# racing_unit.net
KiCad netlist of a schematic drawn in EAGLE
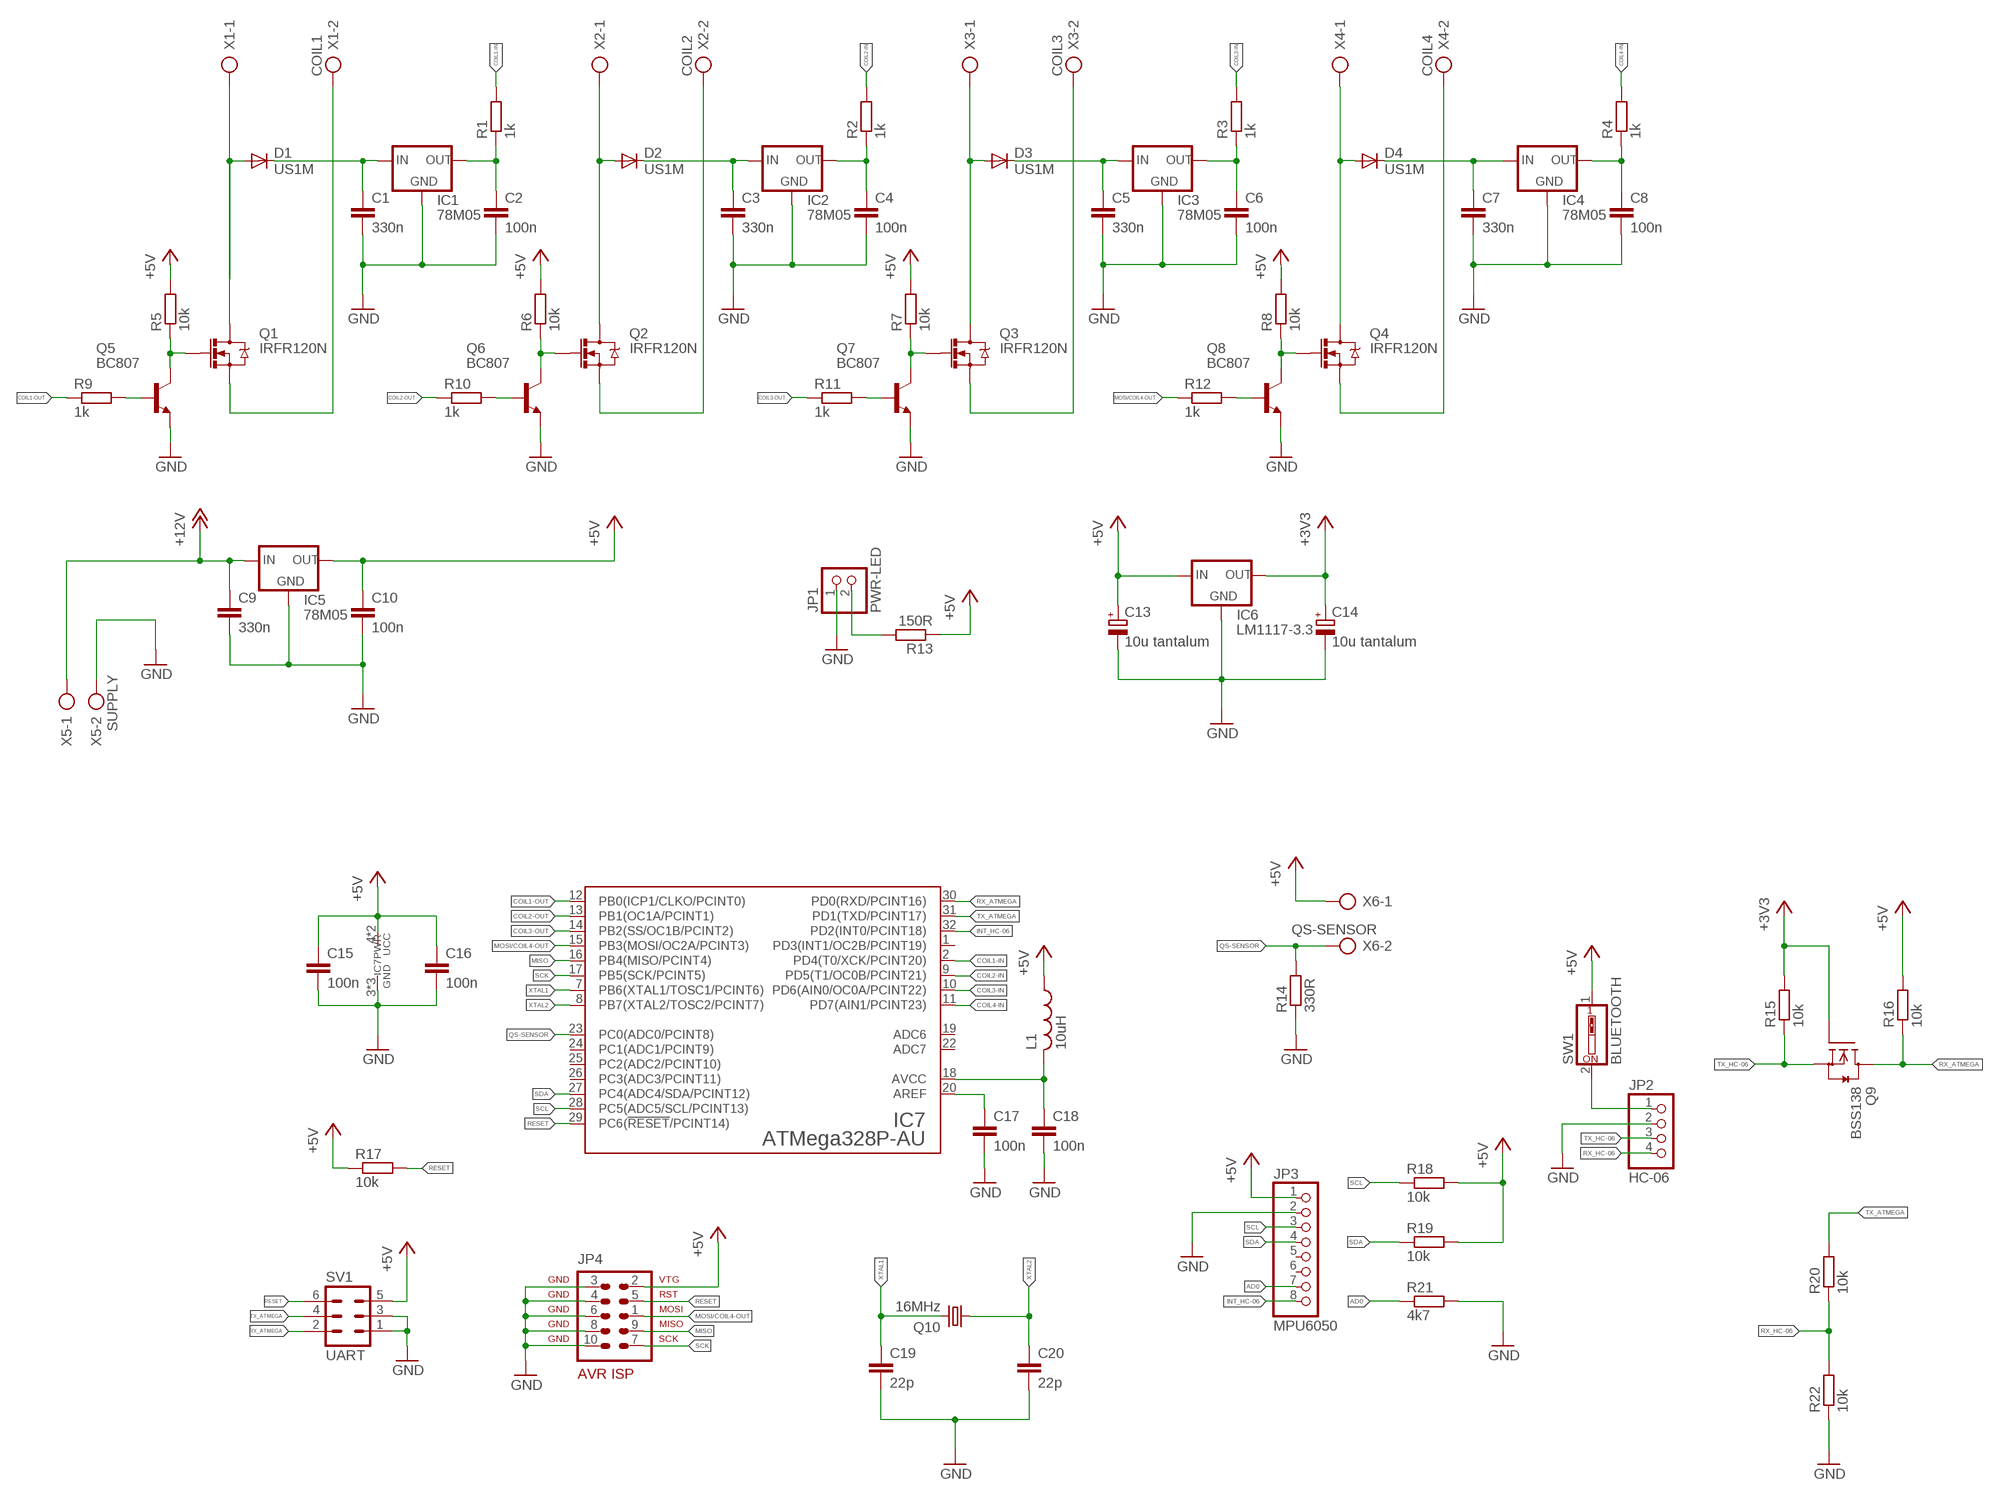
[diagram p0: schematic, sheet 1]

(export (version "E")
  (design (tool "Eeschema 10.0.6"))
  (components
    (comp (ref "C1")
      (value "330n")
      (footprint "eagle-import:C0805")
      (libsource (lib "eagle-import") (part "C-EUC0805"))
    )
    (comp (ref "C2")
      (value "100n")
      (footprint "eagle-import:C0805")
      (libsource (lib "eagle-import") (part "C-EUC0805"))
    )
    (comp (ref "C3")
      (value "330n")
      (footprint "eagle-import:C0805")
      (libsource (lib "eagle-import") (part "C-EUC0805"))
    )
    (comp (ref "C4")
      (value "100n")
      (footprint "eagle-import:C0805")
      (libsource (lib "eagle-import") (part "C-EUC0805"))
    )
    (comp (ref "C5")
      (value "330n")
      (footprint "eagle-import:C0805")
      (libsource (lib "eagle-import") (part "C-EUC0805"))
    )
    (comp (ref "C6")
      (value "100n")
      (footprint "eagle-import:C0805")
      (libsource (lib "eagle-import") (part "C-EUC0805"))
    )
    (comp (ref "C7")
      (value "330n")
      (footprint "eagle-import:C0805")
      (libsource (lib "eagle-import") (part "C-EUC0805"))
    )
    (comp (ref "C8")
      (value "100n")
      (footprint "eagle-import:C0805")
      (libsource (lib "eagle-import") (part "C-EUC0805"))
    )
    (comp (ref "C9")
      (value "330n")
      (footprint "eagle-import:C0805")
      (libsource (lib "eagle-import") (part "C-EUC0805"))
    )
    (comp (ref "C10")
      (value "100n")
      (footprint "eagle-import:C0805")
      (libsource (lib "eagle-import") (part "C-EUC0805"))
    )
    (comp (ref "C13")
      (value "10u tantalum")
      (footprint "eagle-import:A_3216-18R")
      (libsource (lib "eagle-import") (part "CPOL-EUA/3216-18R"))
    )
    (comp (ref "C14")
      (value "10u tantalum")
      (footprint "eagle-import:A_3216-18R")
      (libsource (lib "eagle-import") (part "CPOL-EUA/3216-18R"))
    )
    (comp (ref "C15")
      (value "100n")
      (footprint "eagle-import:C0805")
      (libsource (lib "eagle-import") (part "C-EUC0805"))
    )
    (comp (ref "C16")
      (value "100n")
      (footprint "eagle-import:C0805")
      (libsource (lib "eagle-import") (part "C-EUC0805"))
    )
    (comp (ref "C17")
      (value "100n")
      (footprint "eagle-import:C0805")
      (libsource (lib "eagle-import") (part "C-EUC0805"))
    )
    (comp (ref "C18")
      (value "100n")
      (footprint "eagle-import:C0805")
      (libsource (lib "eagle-import") (part "C-EUC0805"))
    )
    (comp (ref "C19")
      (value "22p")
      (footprint "eagle-import:C0805")
      (libsource (lib "eagle-import") (part "C-EUC0805"))
    )
    (comp (ref "C20")
      (value "22p")
      (footprint "eagle-import:C0805")
      (libsource (lib "eagle-import") (part "C-EUC0805"))
    )
    (comp (ref "D1")
      (value "US1M")
      (footprint "eagle-import:DO214AC")
      (libsource (lib "eagle-import") (part "DIODE-DO214AC"))
    )
    (comp (ref "D2")
      (value "US1M")
      (footprint "eagle-import:DO214AC")
      (libsource (lib "eagle-import") (part "DIODE-DO214AC"))
    )
    (comp (ref "D3")
      (value "US1M")
      (footprint "eagle-import:DO214AC")
      (libsource (lib "eagle-import") (part "DIODE-DO214AC"))
    )
    (comp (ref "D4")
      (value "US1M")
      (footprint "eagle-import:DO214AC")
      (libsource (lib "eagle-import") (part "DIODE-DO214AC"))
    )
    (comp (ref "IC1")
      (value "78M05")
      (footprint "eagle-import:TO252")
      (libsource (lib "eagle-import") (part "LM1117TO252"))
    )
    (comp (ref "IC2")
      (value "78M05")
      (footprint "eagle-import:TO252")
      (libsource (lib "eagle-import") (part "LM1117TO252"))
    )
    (comp (ref "IC3")
      (value "78M05")
      (footprint "eagle-import:TO252")
      (libsource (lib "eagle-import") (part "LM1117TO252"))
    )
    (comp (ref "IC4")
      (value "78M05")
      (footprint "eagle-import:TO252")
      (libsource (lib "eagle-import") (part "LM1117TO252"))
    )
    (comp (ref "IC5")
      (value "78M05")
      (footprint "eagle-import:TO252")
      (libsource (lib "eagle-import") (part "LM1117TO252"))
    )
    (comp (ref "IC6")
      (value "LM1117-3.3")
      (footprint "eagle-import:SOT223")
      (libsource (lib "eagle-import") (part "LM1117"))
    )
    (comp (ref "IC7")
      (value "ATMega328P-AU")
      (footprint "eagle-import:TQFP32-08")
      (libsource (lib "eagle-import") (part "ATMEGA48/88/168/328-AU"))
    )
    (comp (ref "JP1")
      (value "PWR-LED")
      (footprint "eagle-import:1X02")
      (libsource (lib "eagle-import") (part "PINHD-1X2"))
    )
    (comp (ref "JP2")
      (value "HC-06")
      (footprint "eagle-import:1X04")
      (libsource (lib "eagle-import") (part "PINHD-1X4"))
    )
    (comp (ref "JP3")
      (value "MPU6050")
      (footprint "eagle-import:1X08")
      (libsource (lib "eagle-import") (part "PINHD-1X8"))
    )
    (comp (ref "JP4")
      (value "AVR-ISP-10ML")
      (footprint "eagle-import:ML10")
      (libsource (lib "eagle-import") (part "AVR-ISP-10ML"))
    )
    (comp (ref "L1")
      (value "10uH")
      (footprint "eagle-import:0207_10")
      (libsource (lib "eagle-import") (part "L-US0207/10"))
    )
    (comp (ref "Q1")
      (value "IRFR120N")
      (footprint "eagle-import:D-PAK_TO252AA")
      (libsource (lib "eagle-import") (part "MOSFET-NCHANNEL_D-PAK"))
    )
    (comp (ref "Q2")
      (value "IRFR120N")
      (footprint "eagle-import:D-PAK_TO252AA")
      (libsource (lib "eagle-import") (part "MOSFET-NCHANNEL_D-PAK"))
    )
    (comp (ref "Q3")
      (value "IRFR120N")
      (footprint "eagle-import:D-PAK_TO252AA")
      (libsource (lib "eagle-import") (part "MOSFET-NCHANNEL_D-PAK"))
    )
    (comp (ref "Q4")
      (value "IRFR120N")
      (footprint "eagle-import:D-PAK_TO252AA")
      (libsource (lib "eagle-import") (part "MOSFET-NCHANNEL_D-PAK"))
    )
    (comp (ref "Q5")
      (value "BC807")
      (footprint "eagle-import:SOT23-BEC")
      (libsource (lib "eagle-import") (part "BC817SMD-16LT1"))
    )
    (comp (ref "Q6")
      (value "BC807")
      (footprint "eagle-import:SOT23-BEC")
      (libsource (lib "eagle-import") (part "BC817SMD-16LT1"))
    )
    (comp (ref "Q7")
      (value "BC807")
      (footprint "eagle-import:SOT23-BEC")
      (libsource (lib "eagle-import") (part "BC817SMD-16LT1"))
    )
    (comp (ref "Q8")
      (value "BC807")
      (footprint "eagle-import:SOT23-BEC")
      (libsource (lib "eagle-import") (part "BC817SMD-16LT1"))
    )
    (comp (ref "Q9")
      (value "BSS138")
      (footprint "eagle-import:SOT23")
      (libsource (lib "eagle-import") (part "BSS138"))
    )
    (comp (ref "Q10")
      (value "16MHz")
      (footprint "eagle-import:HC49_S")
      (libsource (lib "eagle-import") (part "CRYSTALHC49S"))
    )
    (comp (ref "R1")
      (value "1k")
      (footprint "eagle-import:M0805")
      (libsource (lib "eagle-import") (part "R-EU_M0805"))
    )
    (comp (ref "R2")
      (value "1k")
      (footprint "eagle-import:M0805")
      (libsource (lib "eagle-import") (part "R-EU_M0805"))
    )
    (comp (ref "R3")
      (value "1k")
      (footprint "eagle-import:M0805")
      (libsource (lib "eagle-import") (part "R-EU_M0805"))
    )
    (comp (ref "R4")
      (value "1k")
      (footprint "eagle-import:M0805")
      (libsource (lib "eagle-import") (part "R-EU_M0805"))
    )
    (comp (ref "R5")
      (value "10k")
      (footprint "eagle-import:M0805")
      (libsource (lib "eagle-import") (part "R-EU_M0805"))
    )
    (comp (ref "R6")
      (value "10k")
      (footprint "eagle-import:M0805")
      (libsource (lib "eagle-import") (part "R-EU_M0805"))
    )
    (comp (ref "R7")
      (value "10k")
      (footprint "eagle-import:M0805")
      (libsource (lib "eagle-import") (part "R-EU_M0805"))
    )
    (comp (ref "R8")
      (value "10k")
      (footprint "eagle-import:M0805")
      (libsource (lib "eagle-import") (part "R-EU_M0805"))
    )
    (comp (ref "R9")
      (value "1k")
      (footprint "eagle-import:M0805")
      (libsource (lib "eagle-import") (part "R-EU_M0805"))
    )
    (comp (ref "R10")
      (value "1k")
      (footprint "eagle-import:M0805")
      (libsource (lib "eagle-import") (part "R-EU_M0805"))
    )
    (comp (ref "R11")
      (value "1k")
      (footprint "eagle-import:M0805")
      (libsource (lib "eagle-import") (part "R-EU_M0805"))
    )
    (comp (ref "R12")
      (value "1k")
      (footprint "eagle-import:M0805")
      (libsource (lib "eagle-import") (part "R-EU_M0805"))
    )
    (comp (ref "R13")
      (value "150R")
      (footprint "eagle-import:0204_5")
      (libsource (lib "eagle-import") (part "resistor_R-EU_0204/5"))
    )
    (comp (ref "R14")
      (value "330R")
      (footprint "eagle-import:0204_5")
      (libsource (lib "eagle-import") (part "resistor_R-EU_0204/5"))
    )
    (comp (ref "R15")
      (value "10k")
      (footprint "eagle-import:M0805")
      (libsource (lib "eagle-import") (part "R-EU_M0805"))
    )
    (comp (ref "R16")
      (value "10k")
      (footprint "eagle-import:M0805")
      (libsource (lib "eagle-import") (part "R-EU_M0805"))
    )
    (comp (ref "R17")
      (value "10k")
      (footprint "eagle-import:M0805")
      (libsource (lib "eagle-import") (part "R-EU_M0805"))
    )
    (comp (ref "R18")
      (value "10k")
      (footprint "eagle-import:M0805")
      (libsource (lib "eagle-import") (part "R-EU_M0805"))
    )
    (comp (ref "R19")
      (value "10k")
      (footprint "eagle-import:M0805")
      (libsource (lib "eagle-import") (part "R-EU_M0805"))
    )
    (comp (ref "R20")
      (value "10k")
      (footprint "eagle-import:M0805")
      (libsource (lib "eagle-import") (part "R-EU_M0805"))
    )
    (comp (ref "R21")
      (value "4k7")
      (footprint "eagle-import:M0805")
      (libsource (lib "eagle-import") (part "R-EU_M0805"))
    )
    (comp (ref "R22")
      (value "10k")
      (footprint "eagle-import:M0805")
      (libsource (lib "eagle-import") (part "R-EU_M0805"))
    )
    (comp (ref "SV1")
      (value "UART")
      (footprint "eagle-import:ML6")
      (libsource (lib "eagle-import") (part "ML6"))
    )
    (comp (ref "SW1")
      (value "BLUETOOTH")
      (footprint "eagle-import:EDG-01")
      (libsource (lib "eagle-import") (part "SW_DIP-1"))
    )
    (comp (ref "X1")
      (value "COIL1")
      (footprint "eagle-import:AK500_2")
      (libsource (lib "eagle-import") (part "AK500/2"))
    )
    (comp (ref "X2")
      (value "COIL2")
      (footprint "eagle-import:AK500_2")
      (libsource (lib "eagle-import") (part "AK500/2"))
    )
    (comp (ref "X3")
      (value "COIL3")
      (footprint "eagle-import:AK500_2")
      (libsource (lib "eagle-import") (part "AK500/2"))
    )
    (comp (ref "X4")
      (value "COIL4")
      (footprint "eagle-import:AK500_2")
      (libsource (lib "eagle-import") (part "AK500/2"))
    )
    (comp (ref "X5")
      (value "SUPPLY")
      (footprint "eagle-import:AK500_2")
      (libsource (lib "eagle-import") (part "AK500/2"))
    )
    (comp (ref "X6")
      (value "QS-SENSOR")
      (footprint "eagle-import:AK500_2")
      (libsource (lib "eagle-import") (part "AK500/2"))
    )
  )
  (nets
    (net (code "1") (name "+3V3") (class "Default")
      (node (ref "C14") (pin "+") (pinfunction "+_+") (pintype "passive"))
      (node (ref "IC6") (pin "2") (pinfunction "OUT_2") (pintype "passive"))
      (node (ref "Q9") (pin "1") (pinfunction "G_1") (pintype "passive"))
      (node (ref "R15") (pin "2") (pinfunction "2_2") (pintype "passive"))
    )
    (net (code "2") (name "+5V") (class "Default")
      (node (ref "C10") (pin "1") (pinfunction "1_1") (pintype "passive"))
      (node (ref "C13") (pin "+") (pinfunction "+_+") (pintype "passive"))
      (node (ref "C15") (pin "1") (pinfunction "1_1") (pintype "passive"))
      (node (ref "C16") (pin "1") (pinfunction "1_1") (pintype "passive"))
      (node (ref "IC5") (pin "3") (pinfunction "OUT_3") (pintype "passive"))
      (node (ref "IC6") (pin "3") (pinfunction "IN_3") (pintype "input"))
      (node (ref "IC7") (pin "4") (pinfunction "UCC_4") (pintype "power_in"))
      (node (ref "IC7") (pin "6") (pinfunction "UCC_6") (pintype "power_in"))
      (node (ref "JP3") (pin "1") (pinfunction "1_1") (pintype "passive"))
      (node (ref "JP4") (pin "2") (pinfunction "2_2") (pintype "passive"))
      (node (ref "L1") (pin "1") (pinfunction "1_1") (pintype "passive"))
      (node (ref "R13") (pin "1") (pinfunction "1_1") (pintype "passive"))
      (node (ref "R16") (pin "2") (pinfunction "2_2") (pintype "passive"))
      (node (ref "R17") (pin "1") (pinfunction "1_1") (pintype "passive"))
      (node (ref "R18") (pin "2") (pinfunction "2_2") (pintype "passive"))
      (node (ref "R19") (pin "2") (pinfunction "2_2") (pintype "passive"))
      (node (ref "R5") (pin "2") (pinfunction "2_2") (pintype "passive"))
      (node (ref "R6") (pin "2") (pinfunction "2_2") (pintype "passive"))
      (node (ref "R7") (pin "2") (pinfunction "2_2") (pintype "passive"))
      (node (ref "R8") (pin "2") (pinfunction "2_2") (pintype "passive"))
      (node (ref "SV1") (pin "5") (pinfunction "5_5") (pintype "passive"))
      (node (ref "SW1") (pin "1") (pinfunction "1_1") (pintype "passive"))
      (node (ref "X6") (pin "1") (pinfunction "KL_1") (pintype "passive"))
    )
    (net (code "3") (name "+12V") (class "Default")
      (node (ref "C9") (pin "1") (pinfunction "1_1") (pintype "passive"))
      (node (ref "IC5") (pin "2") (pinfunction "IN_2") (pintype "input"))
      (node (ref "X5") (pin "1") (pinfunction "KL_1") (pintype "passive"))
    )
    (net (code "4") (name "AD0") (class "Default")
      (node (ref "JP3") (pin "7") (pinfunction "7_7") (pintype "passive"))
      (node (ref "R21") (pin "1") (pinfunction "1_1") (pintype "passive"))
    )
    (net (code "5") (name "COIL1-IN") (class "Default")
      (node (ref "IC7") (pin "2") (pinfunction "PD4(T0/XCK/PCINT20)_2") (pintype "bidirectional"))
      (node (ref "R1") (pin "2") (pinfunction "2_2") (pintype "passive"))
    )
    (net (code "6") (name "COIL1-OUT") (class "Default")
      (node (ref "IC7") (pin "12") (pinfunction "PB0(ICP1/CLKO/PCINT0)_12") (pintype "bidirectional"))
      (node (ref "R9") (pin "1") (pinfunction "1_1") (pintype "passive"))
    )
    (net (code "7") (name "COIL2-IN") (class "Default")
      (node (ref "IC7") (pin "9") (pinfunction "PD5(T1/OC0B/PCINT21)_9") (pintype "bidirectional"))
      (node (ref "R2") (pin "2") (pinfunction "2_2") (pintype "passive"))
    )
    (net (code "8") (name "COIL2-OUT") (class "Default")
      (node (ref "IC7") (pin "13") (pinfunction "PB1(OC1A/PCINT1)_13") (pintype "bidirectional"))
      (node (ref "R10") (pin "1") (pinfunction "1_1") (pintype "passive"))
    )
    (net (code "9") (name "COIL3-IN") (class "Default")
      (node (ref "IC7") (pin "10") (pinfunction "PD6(AIN0/OC0A/PCINT22)_10") (pintype "bidirectional"))
      (node (ref "R3") (pin "2") (pinfunction "2_2") (pintype "passive"))
    )
    (net (code "10") (name "COIL3-OUT") (class "Default")
      (node (ref "IC7") (pin "14") (pinfunction "PB2(SS/OC1B/PCINT2)_14") (pintype "bidirectional"))
      (node (ref "R11") (pin "1") (pinfunction "1_1") (pintype "passive"))
    )
    (net (code "11") (name "COIL4-IN") (class "Default")
      (node (ref "IC7") (pin "11") (pinfunction "PD7(AIN1/PCINT23)_11") (pintype "bidirectional"))
      (node (ref "R4") (pin "2") (pinfunction "2_2") (pintype "passive"))
    )
    (net (code "12") (name "GND") (class "Default")
      (node (ref "C1") (pin "2") (pinfunction "2_2") (pintype "passive"))
      (node (ref "C10") (pin "2") (pinfunction "2_2") (pintype "passive"))
      (node (ref "C13") (pin "-") (pinfunction "-_-") (pintype "passive"))
      (node (ref "C14") (pin "-") (pinfunction "-_-") (pintype "passive"))
      (node (ref "C15") (pin "2") (pinfunction "2_2") (pintype "passive"))
      (node (ref "C16") (pin "2") (pinfunction "2_2") (pintype "passive"))
      (node (ref "C17") (pin "2") (pinfunction "2_2") (pintype "passive"))
      (node (ref "C18") (pin "2") (pinfunction "2_2") (pintype "passive"))
      (node (ref "C19") (pin "2") (pinfunction "2_2") (pintype "passive"))
      (node (ref "C2") (pin "2") (pinfunction "2_2") (pintype "passive"))
      (node (ref "C20") (pin "2") (pinfunction "2_2") (pintype "passive"))
      (node (ref "C3") (pin "2") (pinfunction "2_2") (pintype "passive"))
      (node (ref "C4") (pin "2") (pinfunction "2_2") (pintype "passive"))
      (node (ref "C5") (pin "2") (pinfunction "2_2") (pintype "passive"))
      (node (ref "C6") (pin "2") (pinfunction "2_2") (pintype "passive"))
      (node (ref "C7") (pin "2") (pinfunction "2_2") (pintype "passive"))
      (node (ref "C8") (pin "2") (pinfunction "2_2") (pintype "passive"))
      (node (ref "C9") (pin "2") (pinfunction "2_2") (pintype "passive"))
      (node (ref "IC1") (pin "1") (pinfunction "GND_1") (pintype "input"))
      (node (ref "IC2") (pin "1") (pinfunction "GND_1") (pintype "input"))
      (node (ref "IC3") (pin "1") (pinfunction "GND_1") (pintype "input"))
      (node (ref "IC4") (pin "1") (pinfunction "GND_1") (pintype "input"))
      (node (ref "IC5") (pin "1") (pinfunction "GND_1") (pintype "input"))
      (node (ref "IC6") (pin "1") (pinfunction "GND_1") (pintype "input"))
      (node (ref "IC7") (pin "21") (pinfunction "GND_21") (pintype "power_in"))
      (node (ref "IC7") (pin "3") (pinfunction "GND_3") (pintype "power_in"))
      (node (ref "IC7") (pin "5") (pinfunction "GND_5") (pintype "power_in"))
      (node (ref "JP1") (pin "1") (pinfunction "1_1") (pintype "passive"))
      (node (ref "JP2") (pin "2") (pinfunction "2_2") (pintype "passive"))
      (node (ref "JP3") (pin "2") (pinfunction "2_2") (pintype "passive"))
      (node (ref "JP4") (pin "10") (pinfunction "10_10") (pintype "passive"))
      (node (ref "JP4") (pin "3") (pinfunction "3_3") (pintype "passive"))
      (node (ref "JP4") (pin "4") (pinfunction "4_4") (pintype "passive"))
      (node (ref "JP4") (pin "6") (pinfunction "6_6") (pintype "passive"))
      (node (ref "JP4") (pin "8") (pinfunction "8_8") (pintype "passive"))
      (node (ref "Q5") (pin "E") (pinfunction "E_E") (pintype "passive"))
      (node (ref "Q6") (pin "E") (pinfunction "E_E") (pintype "passive"))
      (node (ref "Q7") (pin "E") (pinfunction "E_E") (pintype "passive"))
      (node (ref "Q8") (pin "E") (pinfunction "E_E") (pintype "passive"))
      (node (ref "R14") (pin "1") (pinfunction "1_1") (pintype "passive"))
      (node (ref "R21") (pin "2") (pinfunction "2_2") (pintype "passive"))
      (node (ref "R22") (pin "1") (pinfunction "1_1") (pintype "passive"))
      (node (ref "SV1") (pin "1") (pinfunction "1_1") (pintype "passive"))
      (node (ref "SV1") (pin "3") (pinfunction "3_3") (pintype "passive"))
      (node (ref "X5") (pin "2") (pinfunction "KL_2") (pintype "passive"))
    )
    (net (code "13") (name "INT_HC-06") (class "Default")
      (node (ref "IC7") (pin "32") (pinfunction "PD2(INT0/PCINT18)_32") (pintype "bidirectional"))
      (node (ref "JP3") (pin "8") (pinfunction "8_8") (pintype "passive"))
    )
    (net (code "14") (name "MISO") (class "Default")
      (node (ref "IC7") (pin "16") (pinfunction "PB4(MISO/PCINT4)_16") (pintype "bidirectional"))
      (node (ref "JP4") (pin "9") (pinfunction "9_9") (pintype "passive"))
    )
    (net (code "15") (name "MOSI{slash}COIL4-OUT") (class "Default")
      (node (ref "IC7") (pin "15") (pinfunction "PB3(MOSI/OC2A/PCINT3)_15") (pintype "bidirectional"))
      (node (ref "JP4") (pin "1") (pinfunction "1_1") (pintype "passive"))
      (node (ref "R12") (pin "1") (pinfunction "1_1") (pintype "passive"))
    )
    (net (code "16") (name "Net-(IC1-IN)") (class "Default")
      (node (ref "C1") (pin "1") (pinfunction "1_1") (pintype "passive"))
      (node (ref "D1") (pin "C") (pinfunction "C_C") (pintype "passive"))
      (node (ref "IC1") (pin "2") (pinfunction "IN_2") (pintype "input"))
    )
    (net (code "17") (name "Net-(IC1-OUT)") (class "Default")
      (node (ref "C2") (pin "1") (pinfunction "1_1") (pintype "passive"))
      (node (ref "IC1") (pin "3") (pinfunction "OUT_3") (pintype "passive"))
      (node (ref "R1") (pin "1") (pinfunction "1_1") (pintype "passive"))
    )
    (net (code "18") (name "Net-(IC2-IN)") (class "Default")
      (node (ref "C3") (pin "1") (pinfunction "1_1") (pintype "passive"))
      (node (ref "D2") (pin "C") (pinfunction "C_C") (pintype "passive"))
      (node (ref "IC2") (pin "2") (pinfunction "IN_2") (pintype "input"))
    )
    (net (code "19") (name "Net-(IC2-OUT)") (class "Default")
      (node (ref "C4") (pin "1") (pinfunction "1_1") (pintype "passive"))
      (node (ref "IC2") (pin "3") (pinfunction "OUT_3") (pintype "passive"))
      (node (ref "R2") (pin "1") (pinfunction "1_1") (pintype "passive"))
    )
    (net (code "20") (name "Net-(IC3-IN)") (class "Default")
      (node (ref "C5") (pin "1") (pinfunction "1_1") (pintype "passive"))
      (node (ref "D3") (pin "C") (pinfunction "C_C") (pintype "passive"))
      (node (ref "IC3") (pin "2") (pinfunction "IN_2") (pintype "input"))
    )
    (net (code "21") (name "Net-(IC3-OUT)") (class "Default")
      (node (ref "C6") (pin "1") (pinfunction "1_1") (pintype "passive"))
      (node (ref "IC3") (pin "3") (pinfunction "OUT_3") (pintype "passive"))
      (node (ref "R3") (pin "1") (pinfunction "1_1") (pintype "passive"))
    )
    (net (code "22") (name "Net-(IC4-IN)") (class "Default")
      (node (ref "C7") (pin "1") (pinfunction "1_1") (pintype "passive"))
      (node (ref "D4") (pin "C") (pinfunction "C_C") (pintype "passive"))
      (node (ref "IC4") (pin "2") (pinfunction "IN_2") (pintype "input"))
    )
    (net (code "23") (name "Net-(IC4-OUT)") (class "Default")
      (node (ref "C8") (pin "1") (pinfunction "1_1") (pintype "passive"))
      (node (ref "IC4") (pin "3") (pinfunction "OUT_3") (pintype "passive"))
      (node (ref "R4") (pin "1") (pinfunction "1_1") (pintype "passive"))
    )
    (net (code "24") (name "Net-(IC7A-AREF)") (class "Default")
      (node (ref "C17") (pin "1") (pinfunction "1_1") (pintype "passive"))
      (node (ref "IC7") (pin "20") (pinfunction "AREF_20") (pintype "passive"))
    )
    (net (code "25") (name "Net-(IC7A-AVCC)") (class "Default")
      (node (ref "C18") (pin "1") (pinfunction "1_1") (pintype "passive"))
      (node (ref "IC7") (pin "18") (pinfunction "AVCC_18") (pintype "power_in"))
      (node (ref "L1") (pin "2") (pinfunction "2_2") (pintype "passive"))
    )
    (net (code "26") (name "Net-(JP1-Pad2)") (class "Default")
      (node (ref "JP1") (pin "2") (pinfunction "2_2") (pintype "passive"))
      (node (ref "R13") (pin "2") (pinfunction "2_2") (pintype "passive"))
    )
    (net (code "27") (name "Net-(JP2-Pad1)") (class "Default")
      (node (ref "JP2") (pin "1") (pinfunction "1_1") (pintype "passive"))
      (node (ref "SW1") (pin "2") (pinfunction "2_2") (pintype "passive"))
    )
    (net (code "28") (name "Net-(Q1-D)") (class "Default")
      (node (ref "D1") (pin "A") (pinfunction "A_A") (pintype "passive"))
      (node (ref "Q1") (pin "2") (pinfunction "D_2") (pintype "passive"))
      (node (ref "X1") (pin "1") (pinfunction "KL_1") (pintype "passive"))
    )
    (net (code "29") (name "Net-(Q1-G)") (class "Default")
      (node (ref "Q1") (pin "1") (pinfunction "G_1") (pintype "passive"))
      (node (ref "Q5") (pin "C") (pinfunction "C_C") (pintype "passive"))
      (node (ref "R5") (pin "1") (pinfunction "1_1") (pintype "passive"))
    )
    (net (code "30") (name "Net-(Q1-S)") (class "Default")
      (node (ref "Q1") (pin "3") (pinfunction "S_3") (pintype "passive"))
      (node (ref "X1") (pin "2") (pinfunction "KL_2") (pintype "passive"))
    )
    (net (code "31") (name "Net-(Q2-D)") (class "Default")
      (node (ref "D2") (pin "A") (pinfunction "A_A") (pintype "passive"))
      (node (ref "Q2") (pin "2") (pinfunction "D_2") (pintype "passive"))
      (node (ref "X2") (pin "1") (pinfunction "KL_1") (pintype "passive"))
    )
    (net (code "32") (name "Net-(Q2-G)") (class "Default")
      (node (ref "Q2") (pin "1") (pinfunction "G_1") (pintype "passive"))
      (node (ref "Q6") (pin "C") (pinfunction "C_C") (pintype "passive"))
      (node (ref "R6") (pin "1") (pinfunction "1_1") (pintype "passive"))
    )
    (net (code "33") (name "Net-(Q2-S)") (class "Default")
      (node (ref "Q2") (pin "3") (pinfunction "S_3") (pintype "passive"))
      (node (ref "X2") (pin "2") (pinfunction "KL_2") (pintype "passive"))
    )
    (net (code "34") (name "Net-(Q3-D)") (class "Default")
      (node (ref "D3") (pin "A") (pinfunction "A_A") (pintype "passive"))
      (node (ref "Q3") (pin "2") (pinfunction "D_2") (pintype "passive"))
      (node (ref "X3") (pin "1") (pinfunction "KL_1") (pintype "passive"))
    )
    (net (code "35") (name "Net-(Q3-G)") (class "Default")
      (node (ref "Q3") (pin "1") (pinfunction "G_1") (pintype "passive"))
      (node (ref "Q7") (pin "C") (pinfunction "C_C") (pintype "passive"))
      (node (ref "R7") (pin "1") (pinfunction "1_1") (pintype "passive"))
    )
    (net (code "36") (name "Net-(Q3-S)") (class "Default")
      (node (ref "Q3") (pin "3") (pinfunction "S_3") (pintype "passive"))
      (node (ref "X3") (pin "2") (pinfunction "KL_2") (pintype "passive"))
    )
    (net (code "37") (name "Net-(Q4-D)") (class "Default")
      (node (ref "D4") (pin "A") (pinfunction "A_A") (pintype "passive"))
      (node (ref "Q4") (pin "2") (pinfunction "D_2") (pintype "passive"))
      (node (ref "X4") (pin "1") (pinfunction "KL_1") (pintype "passive"))
    )
    (net (code "38") (name "Net-(Q4-G)") (class "Default")
      (node (ref "Q4") (pin "1") (pinfunction "G_1") (pintype "passive"))
      (node (ref "Q8") (pin "C") (pinfunction "C_C") (pintype "passive"))
      (node (ref "R8") (pin "1") (pinfunction "1_1") (pintype "passive"))
    )
    (net (code "39") (name "Net-(Q4-S)") (class "Default")
      (node (ref "Q4") (pin "3") (pinfunction "S_3") (pintype "passive"))
      (node (ref "X4") (pin "2") (pinfunction "KL_2") (pintype "passive"))
    )
    (net (code "40") (name "Net-(Q5-PadB)") (class "Default")
      (node (ref "Q5") (pin "B") (pinfunction "B_B") (pintype "passive"))
      (node (ref "R9") (pin "2") (pinfunction "2_2") (pintype "passive"))
    )
    (net (code "41") (name "Net-(Q6-PadB)") (class "Default")
      (node (ref "Q6") (pin "B") (pinfunction "B_B") (pintype "passive"))
      (node (ref "R10") (pin "2") (pinfunction "2_2") (pintype "passive"))
    )
    (net (code "42") (name "Net-(Q7-PadB)") (class "Default")
      (node (ref "Q7") (pin "B") (pinfunction "B_B") (pintype "passive"))
      (node (ref "R11") (pin "2") (pinfunction "2_2") (pintype "passive"))
    )
    (net (code "43") (name "Net-(Q8-PadB)") (class "Default")
      (node (ref "Q8") (pin "B") (pinfunction "B_B") (pintype "passive"))
      (node (ref "R12") (pin "2") (pinfunction "2_2") (pintype "passive"))
    )
    (net (code "44") (name "QS-SENSOR") (class "Default")
      (node (ref "IC7") (pin "23") (pinfunction "PC0(ADC0/PCINT8)_23") (pintype "bidirectional"))
      (node (ref "R14") (pin "2") (pinfunction "2_2") (pintype "passive"))
      (node (ref "X6") (pin "2") (pinfunction "KL_2") (pintype "passive"))
    )
    (net (code "45") (name "RESET") (class "Default")
      (node (ref "IC7") (pin "29") (pinfunction "PC6(~{RESET}/PCINT14)_29") (pintype "bidirectional"))
      (node (ref "JP4") (pin "5") (pinfunction "5_5") (pintype "passive"))
      (node (ref "R17") (pin "2") (pinfunction "2_2") (pintype "passive"))
      (node (ref "SV1") (pin "6") (pinfunction "6_6") (pintype "passive"))
    )
    (net (code "46") (name "RX_ATMEGA") (class "Default")
      (node (ref "IC7") (pin "30") (pinfunction "PD0(RXD/PCINT16)_30") (pintype "bidirectional"))
      (node (ref "Q9") (pin "3") (pinfunction "D_3") (pintype "passive"))
      (node (ref "R16") (pin "1") (pinfunction "1_1") (pintype "passive"))
      (node (ref "SV1") (pin "2") (pinfunction "2_2") (pintype "passive"))
    )
    (net (code "47") (name "RX_HC-06") (class "Default")
      (node (ref "JP2") (pin "4") (pinfunction "4_4") (pintype "passive"))
      (node (ref "R20") (pin "1") (pinfunction "1_1") (pintype "passive"))
      (node (ref "R22") (pin "2") (pinfunction "2_2") (pintype "passive"))
    )
    (net (code "48") (name "SCK") (class "Default")
      (node (ref "IC7") (pin "17") (pinfunction "PB5(SCK/PCINT5)_17") (pintype "bidirectional"))
      (node (ref "JP4") (pin "7") (pinfunction "7_7") (pintype "passive"))
    )
    (net (code "49") (name "SCL") (class "Default")
      (node (ref "IC7") (pin "28") (pinfunction "PC5(ADC5/SCL/PCINT13)_28") (pintype "bidirectional"))
      (node (ref "JP3") (pin "3") (pinfunction "3_3") (pintype "passive"))
      (node (ref "R18") (pin "1") (pinfunction "1_1") (pintype "passive"))
    )
    (net (code "50") (name "SDA") (class "Default")
      (node (ref "IC7") (pin "27") (pinfunction "PC4(ADC4/SDA/PCINT12)_27") (pintype "bidirectional"))
      (node (ref "JP3") (pin "4") (pinfunction "4_4") (pintype "passive"))
      (node (ref "R19") (pin "1") (pinfunction "1_1") (pintype "passive"))
    )
    (net (code "51") (name "TX_ATMEGA") (class "Default")
      (node (ref "IC7") (pin "31") (pinfunction "PD1(TXD/PCINT17)_31") (pintype "bidirectional"))
      (node (ref "R20") (pin "2") (pinfunction "2_2") (pintype "passive"))
      (node (ref "SV1") (pin "4") (pinfunction "4_4") (pintype "passive"))
    )
    (net (code "52") (name "TX_HC-06") (class "Default")
      (node (ref "JP2") (pin "3") (pinfunction "3_3") (pintype "passive"))
      (node (ref "Q9") (pin "2") (pinfunction "S_2") (pintype "passive"))
      (node (ref "R15") (pin "1") (pinfunction "1_1") (pintype "passive"))
    )
    (net (code "53") (name "XTAL1") (class "Default")
      (node (ref "C19") (pin "1") (pinfunction "1_1") (pintype "passive"))
      (node (ref "IC7") (pin "7") (pinfunction "PB6(XTAL1/TOSC1/PCINT6)_7") (pintype "bidirectional"))
      (node (ref "Q10") (pin "2") (pinfunction "2_2") (pintype "passive"))
    )
    (net (code "54") (name "XTAL2") (class "Default")
      (node (ref "C20") (pin "1") (pinfunction "1_1") (pintype "passive"))
      (node (ref "IC7") (pin "8") (pinfunction "PB7(XTAL2/TOSC2/PCINT7)_8") (pintype "bidirectional"))
      (node (ref "Q10") (pin "1") (pinfunction "1_1") (pintype "passive"))
    )
    (net (code "55") (name "unconnected-(IC7A-ADC6-Pad19)") (class "Default")
      (node (ref "IC7") (pin "19") (pinfunction "ADC6_19") (pintype "passive"))
    )
    (net (code "56") (name "unconnected-(IC7A-ADC7-Pad22)") (class "Default")
      (node (ref "IC7") (pin "22") (pinfunction "ADC7_22") (pintype "passive"))
    )
    (net (code "57") (name "unconnected-(IC7A-PC1(ADC1{slash}PCINT9)-Pad24)") (class "Default")
      (node (ref "IC7") (pin "24") (pinfunction "PC1(ADC1/PCINT9)_24") (pintype "bidirectional"))
    )
    (net (code "58") (name "unconnected-(IC7A-PC2(ADC2{slash}PCINT10)-Pad25)") (class "Default")
      (node (ref "IC7") (pin "25") (pinfunction "PC2(ADC2/PCINT10)_25") (pintype "bidirectional"))
    )
    (net (code "59") (name "unconnected-(IC7A-PC3(ADC3{slash}PCINT11)-Pad26)") (class "Default")
      (node (ref "IC7") (pin "26") (pinfunction "PC3(ADC3/PCINT11)_26") (pintype "bidirectional"))
    )
    (net (code "60") (name "unconnected-(IC7A-PD3(INT1{slash}OC2B{slash}PCINT19)-Pad1)") (class "Default")
      (node (ref "IC7") (pin "1") (pinfunction "PD3(INT1/OC2B/PCINT19)_1") (pintype "bidirectional"))
    )
    (net (code "61") (name "unconnected-(JP3-Pad5)") (class "Default")
      (node (ref "JP3") (pin "5") (pinfunction "5_5") (pintype "passive"))
    )
    (net (code "62") (name "unconnected-(JP3-Pad6)") (class "Default")
      (node (ref "JP3") (pin "6") (pinfunction "6_6") (pintype "passive"))
    )
  )
)
